# openSX70-dongle_v2-8.net
KiCad netlist of a schematic drawn in EAGLE
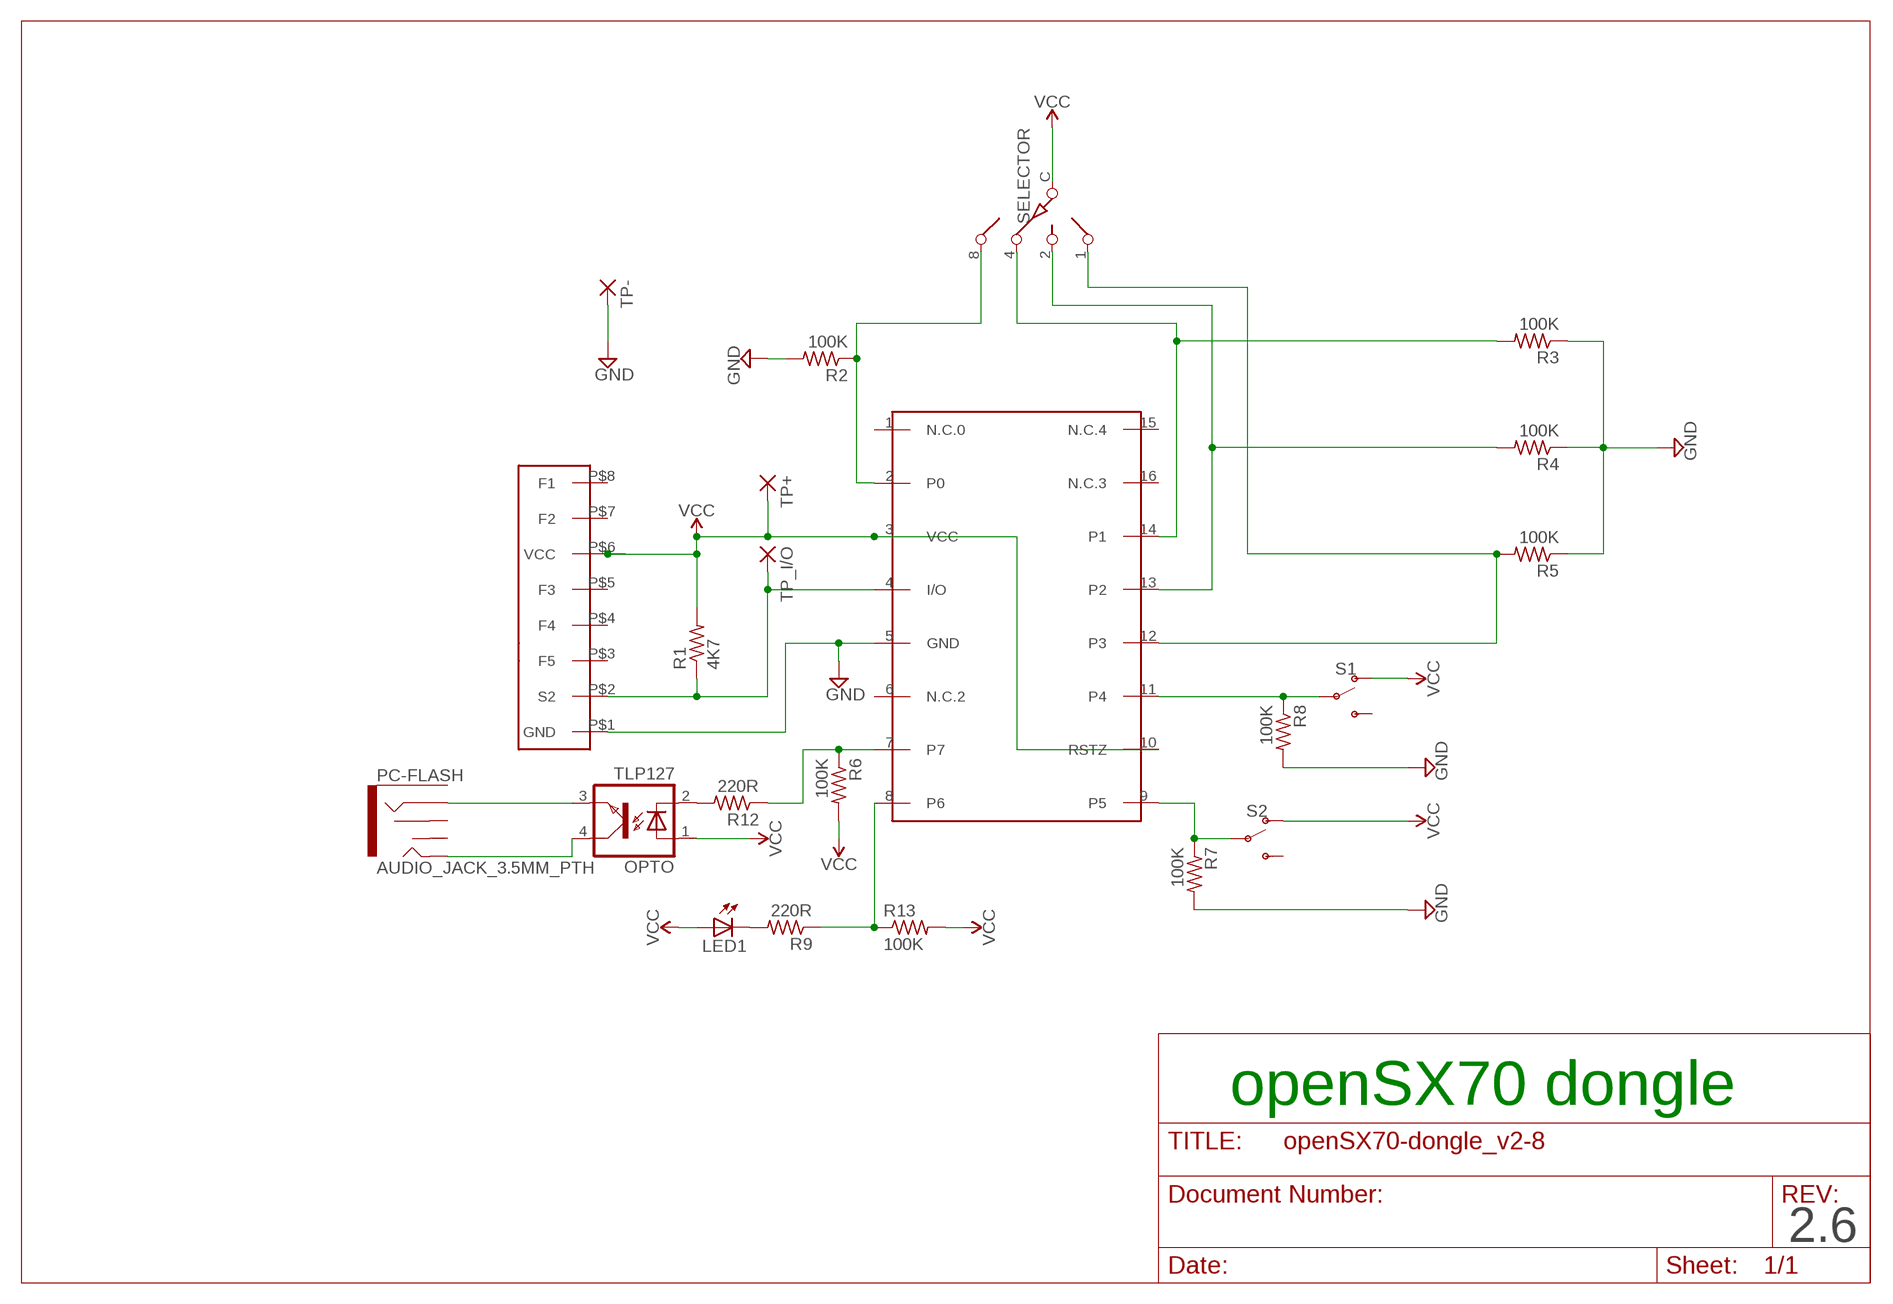
[diagram p0: schematic, sheet 1]

(export (version "E")
  (design (tool "Eeschema 10.0.6"))
  (components
    (comp (ref "DS2408")
      (value "DS2408")
      (footprint "eagle-import:SO16")
      (libsource (lib "eagle-import") (part "DS2408"))
    )
    (comp (ref "LED1")
      (value "LED3MM")
      (footprint "eagle-import:LED3MM")
      (libsource (lib "eagle-import") (part "LED3MM"))
    )
    (comp (ref "OPTO")
      (value "TLP127")
      (footprint "eagle-import:SO-4")
      (libsource (lib "eagle-import") (part "TLP127"))
    )
    (comp (ref "PC-FLASH")
      (value "AUDIO_JACK_3.5MM_PTH")
      (footprint "eagle-import:AUDIO-JACK")
      (libsource (lib "eagle-import") (part "AUDIO_JACK_3.5MM_PTH"))
    )
    (comp (ref "R1")
      (value "4K7")
      (footprint "eagle-import:M0805")
      (libsource (lib "eagle-import") (part "R-US_M0805"))
    )
    (comp (ref "R2")
      (value "100K")
      (footprint "eagle-import:M0805")
      (libsource (lib "eagle-import") (part "R-US_M0805"))
    )
    (comp (ref "R3")
      (value "100K")
      (footprint "eagle-import:M0805")
      (libsource (lib "eagle-import") (part "R-US_M0805"))
    )
    (comp (ref "R4")
      (value "100K")
      (footprint "eagle-import:M0805")
      (libsource (lib "eagle-import") (part "R-US_M0805"))
    )
    (comp (ref "R5")
      (value "100K")
      (footprint "eagle-import:M0805")
      (libsource (lib "eagle-import") (part "R-US_M0805"))
    )
    (comp (ref "R6")
      (value "100K")
      (footprint "eagle-import:M0805")
      (libsource (lib "eagle-import") (part "R-US_M0805"))
    )
    (comp (ref "R7")
      (value "100K")
      (footprint "eagle-import:M0805")
      (libsource (lib "eagle-import") (part "R-US_M0805"))
    )
    (comp (ref "R8")
      (value "100K")
      (footprint "eagle-import:M0805")
      (libsource (lib "eagle-import") (part "R-US_M0805"))
    )
    (comp (ref "R9")
      (value "220R")
      (footprint "eagle-import:M0805")
      (libsource (lib "eagle-import") (part "R-US_M0805"))
    )
    (comp (ref "R12")
      (value "220R")
      (footprint "eagle-import:M0805")
      (libsource (lib "eagle-import") (part "R-US_M0805"))
    )
    (comp (ref "R13")
      (value "100K")
      (footprint "eagle-import:M0805")
      (libsource (lib "eagle-import") (part "R-US_M0805"))
    )
    (comp (ref "S1")
      (value "SWITCH-SPDT-SMD-RIGHT-ANGLE")
      (footprint "eagle-import:SWITCH_SPST_SMD_A")
      (libsource (lib "eagle-import") (part "SWITCH-SPDT-SMD-RIGHT-ANGLE"))
    )
    (comp (ref "S2")
      (value "SWITCH-SPDT-SMD-RIGHT-ANGLE")
      (footprint "eagle-import:SWITCH_SPST_SMD_A")
      (libsource (lib "eagle-import") (part "SWITCH-SPDT-SMD-RIGHT-ANGLE"))
    )
    (comp (ref "SELECTOR")
      (value "SW-C16")
      (footprint "eagle-import:SW-C16")
      (libsource (lib "eagle-import") (part "SW-C16"))
    )
    (comp (ref "TP+")
      (value "SMD2")
      (footprint "eagle-import:SMD1,27-2,54")
      (libsource (lib "eagle-import") (part "SMD2"))
    )
    (comp (ref "TP-")
      (value "SMD2")
      (footprint "eagle-import:SMD1,27-2,54")
      (libsource (lib "eagle-import") (part "SMD2"))
    )
    (comp (ref "TP_I/O")
      (value "SMD2")
      (footprint "eagle-import:SMD1,27-2,54")
      (libsource (lib "eagle-import") (part "SMD2"))
    )
    (comp (ref "U$1")
      (value "FLASH-EDGE-CONNECTOR")
      (footprint "eagle-import:FLASH-EDGE-8")
      (libsource (lib "eagle-import") (part "FLASH-EDGE-CONNECTOR"))
    )
  )
  (nets
    (net (code "1") (name "GND") (class "Default")
      (node (ref "DS2408") (pin "5") (pinfunction "GND_5") (pintype "bidirectional"))
      (node (ref "R2") (pin "2") (pinfunction "2_2") (pintype "passive"))
      (node (ref "R3") (pin "1") (pinfunction "1_1") (pintype "passive"))
      (node (ref "R4") (pin "1") (pinfunction "1_1") (pintype "passive"))
      (node (ref "R5") (pin "1") (pinfunction "1_1") (pintype "passive"))
      (node (ref "R7") (pin "2") (pinfunction "2_2") (pintype "passive"))
      (node (ref "R8") (pin "2") (pinfunction "2_2") (pintype "passive"))
      (node (ref "TP-") (pin "1") (pinfunction "P_1") (pintype "passive"))
      (node (ref "U$1") (pin "P$1") (pinfunction "GND_P$1") (pintype "bidirectional"))
    )
    (net (code "2") (name "Net-(DS2408-I{slash}O)") (class "Default")
      (node (ref "DS2408") (pin "4") (pinfunction "I/O_4") (pintype "bidirectional"))
      (node (ref "R1") (pin "1") (pinfunction "1_1") (pintype "passive"))
      (node (ref "TP_I/O") (pin "1") (pinfunction "P_1") (pintype "passive"))
      (node (ref "U$1") (pin "P$2") (pinfunction "S2_P$2") (pintype "bidirectional"))
    )
    (net (code "3") (name "Net-(DS2408-P0)") (class "Default")
      (node (ref "DS2408") (pin "2") (pinfunction "P0_2") (pintype "bidirectional"))
      (node (ref "R2") (pin "1") (pinfunction "1_1") (pintype "passive"))
      (node (ref "SELECTOR") (pin "8") (pinfunction "8_8") (pintype "passive"))
    )
    (net (code "4") (name "Net-(DS2408-P1)") (class "Default")
      (node (ref "DS2408") (pin "14") (pinfunction "P1_14") (pintype "bidirectional"))
      (node (ref "R3") (pin "2") (pinfunction "2_2") (pintype "passive"))
      (node (ref "SELECTOR") (pin "4") (pinfunction "4_4") (pintype "passive"))
    )
    (net (code "5") (name "Net-(DS2408-P2)") (class "Default")
      (node (ref "DS2408") (pin "13") (pinfunction "P2_13") (pintype "bidirectional"))
      (node (ref "R4") (pin "2") (pinfunction "2_2") (pintype "passive"))
      (node (ref "SELECTOR") (pin "2") (pinfunction "2_2") (pintype "passive"))
    )
    (net (code "6") (name "Net-(DS2408-P3)") (class "Default")
      (node (ref "DS2408") (pin "12") (pinfunction "P3_12") (pintype "bidirectional"))
      (node (ref "R5") (pin "2") (pinfunction "2_2") (pintype "passive"))
      (node (ref "SELECTOR") (pin "1") (pinfunction "1_1") (pintype "passive"))
    )
    (net (code "7") (name "Net-(DS2408-P4)") (class "Default")
      (node (ref "DS2408") (pin "11") (pinfunction "P4_11") (pintype "bidirectional"))
      (node (ref "R8") (pin "1") (pinfunction "1_1") (pintype "passive"))
      (node (ref "S1") (pin "2") (pinfunction "P_2") (pintype "passive"))
    )
    (net (code "8") (name "Net-(DS2408-P5)") (class "Default")
      (node (ref "DS2408") (pin "9") (pinfunction "P5_9") (pintype "bidirectional"))
      (node (ref "R7") (pin "1") (pinfunction "1_1") (pintype "passive"))
      (node (ref "S2") (pin "2") (pinfunction "P_2") (pintype "passive"))
    )
    (net (code "9") (name "Net-(DS2408-P6)") (class "Default")
      (node (ref "DS2408") (pin "8") (pinfunction "P6_8") (pintype "bidirectional"))
      (node (ref "R13") (pin "1") (pinfunction "1_1") (pintype "passive"))
      (node (ref "R9") (pin "1") (pinfunction "1_1") (pintype "passive"))
    )
    (net (code "10") (name "Net-(DS2408-P7)") (class "Default")
      (node (ref "DS2408") (pin "7") (pinfunction "P7_7") (pintype "bidirectional"))
      (node (ref "R12") (pin "1") (pinfunction "1_1") (pintype "passive"))
      (node (ref "R6") (pin "1") (pinfunction "1_1") (pintype "passive"))
    )
    (net (code "11") (name "Net-(LED1-C)") (class "Default")
      (node (ref "LED1") (pin "K") (pinfunction "C_K") (pintype "passive"))
      (node (ref "R9") (pin "2") (pinfunction "2_2") (pintype "passive"))
    )
    (net (code "12") (name "Net-(OPTO-C)") (class "Default")
      (node (ref "OPTO") (pin "2") (pinfunction "C_2") (pintype "passive"))
      (node (ref "R12") (pin "2") (pinfunction "2_2") (pintype "passive"))
    )
    (net (code "13") (name "Net-(OPTO-COL)") (class "Default")
      (node (ref "OPTO") (pin "4") (pinfunction "COL_4") (pintype "passive"))
      (node (ref "PC-FLASH") (pin "TIP") (pinfunction "TIP_TIP") (pintype "bidirectional"))
    )
    (net (code "14") (name "Net-(OPTO-EMIT)") (class "Default")
      (node (ref "OPTO") (pin "3") (pinfunction "EMIT_3") (pintype "passive"))
      (node (ref "PC-FLASH") (pin "RING") (pinfunction "RING_RING") (pintype "bidirectional"))
    )
    (net (code "15") (name "VCC") (class "Default")
      (node (ref "DS2408") (pin "10") (pinfunction "RSTZ_10") (pintype "bidirectional"))
      (node (ref "DS2408") (pin "3") (pinfunction "VCC_3") (pintype "bidirectional"))
      (node (ref "LED1") (pin "A") (pinfunction "A_A") (pintype "passive"))
      (node (ref "OPTO") (pin "1") (pinfunction "A_1") (pintype "passive"))
      (node (ref "R1") (pin "2") (pinfunction "2_2") (pintype "passive"))
      (node (ref "R13") (pin "2") (pinfunction "2_2") (pintype "passive"))
      (node (ref "R6") (pin "2") (pinfunction "2_2") (pintype "passive"))
      (node (ref "S1") (pin "1") (pinfunction "O_1") (pintype "passive"))
      (node (ref "S2") (pin "1") (pinfunction "O_1") (pintype "passive"))
      (node (ref "SELECTOR") (pin "C") (pinfunction "C_C") (pintype "passive"))
      (node (ref "TP+") (pin "1") (pinfunction "P_1") (pintype "passive"))
      (node (ref "U$1") (pin "P$6") (pinfunction "VCC_P$6") (pintype "bidirectional"))
    )
    (net (code "16") (name "unconnected-(DS2408-N.C.0-Pad1)") (class "Default")
      (node (ref "DS2408") (pin "1") (pinfunction "N.C.0_1") (pintype "bidirectional"))
    )
    (net (code "17") (name "unconnected-(DS2408-N.C.2-Pad6)") (class "Default")
      (node (ref "DS2408") (pin "6") (pinfunction "N.C.2_6") (pintype "bidirectional"))
    )
    (net (code "18") (name "unconnected-(DS2408-N.C.3-Pad16)") (class "Default")
      (node (ref "DS2408") (pin "16") (pinfunction "N.C.3_16") (pintype "bidirectional"))
    )
    (net (code "19") (name "unconnected-(DS2408-N.C.4-Pad15)") (class "Default")
      (node (ref "DS2408") (pin "15") (pinfunction "N.C.4_15") (pintype "bidirectional"))
    )
    (net (code "20") (name "unconnected-(PC-FLASH-PadRSH)") (class "Default")
      (node (ref "PC-FLASH") (pin "RSH") (pinfunction "RSH_RSH") (pintype "bidirectional"))
    )
    (net (code "21") (name "unconnected-(PC-FLASH-PadSLEEVE)") (class "Default")
      (node (ref "PC-FLASH") (pin "SLEEVE") (pinfunction "SLEEVE_SLEEVE") (pintype "bidirectional"))
    )
    (net (code "22") (name "unconnected-(PC-FLASH-PadTSH)") (class "Default")
      (node (ref "PC-FLASH") (pin "TSH") (pinfunction "TSH_TSH") (pintype "bidirectional"))
    )
    (net (code "23") (name "unconnected-(S1-S-Pad3)") (class "Default")
      (node (ref "S1") (pin "3") (pinfunction "S_3") (pintype "passive"))
    )
    (net (code "24") (name "unconnected-(S2-S-Pad3)") (class "Default")
      (node (ref "S2") (pin "3") (pinfunction "S_3") (pintype "passive"))
    )
    (net (code "25") (name "unconnected-(U$1-F1-PadP$8)") (class "Default")
      (node (ref "U$1") (pin "P$8") (pinfunction "F1_P$8") (pintype "bidirectional"))
    )
    (net (code "26") (name "unconnected-(U$1-F2-PadP$7)") (class "Default")
      (node (ref "U$1") (pin "P$7") (pinfunction "F2_P$7") (pintype "bidirectional"))
    )
    (net (code "27") (name "unconnected-(U$1-F3-PadP$5)") (class "Default")
      (node (ref "U$1") (pin "P$5") (pinfunction "F3_P$5") (pintype "bidirectional"))
    )
    (net (code "28") (name "unconnected-(U$1-F4-PadP$4)") (class "Default")
      (node (ref "U$1") (pin "P$4") (pinfunction "F4_P$4") (pintype "bidirectional"))
    )
    (net (code "29") (name "unconnected-(U$1-F5-PadP$3)") (class "Default")
      (node (ref "U$1") (pin "P$3") (pinfunction "F5_P$3") (pintype "bidirectional"))
    )
  )
)
